# RTL8153B_DemoSCH.net
KiCad netlist of a schematic drawn in Altium Designer
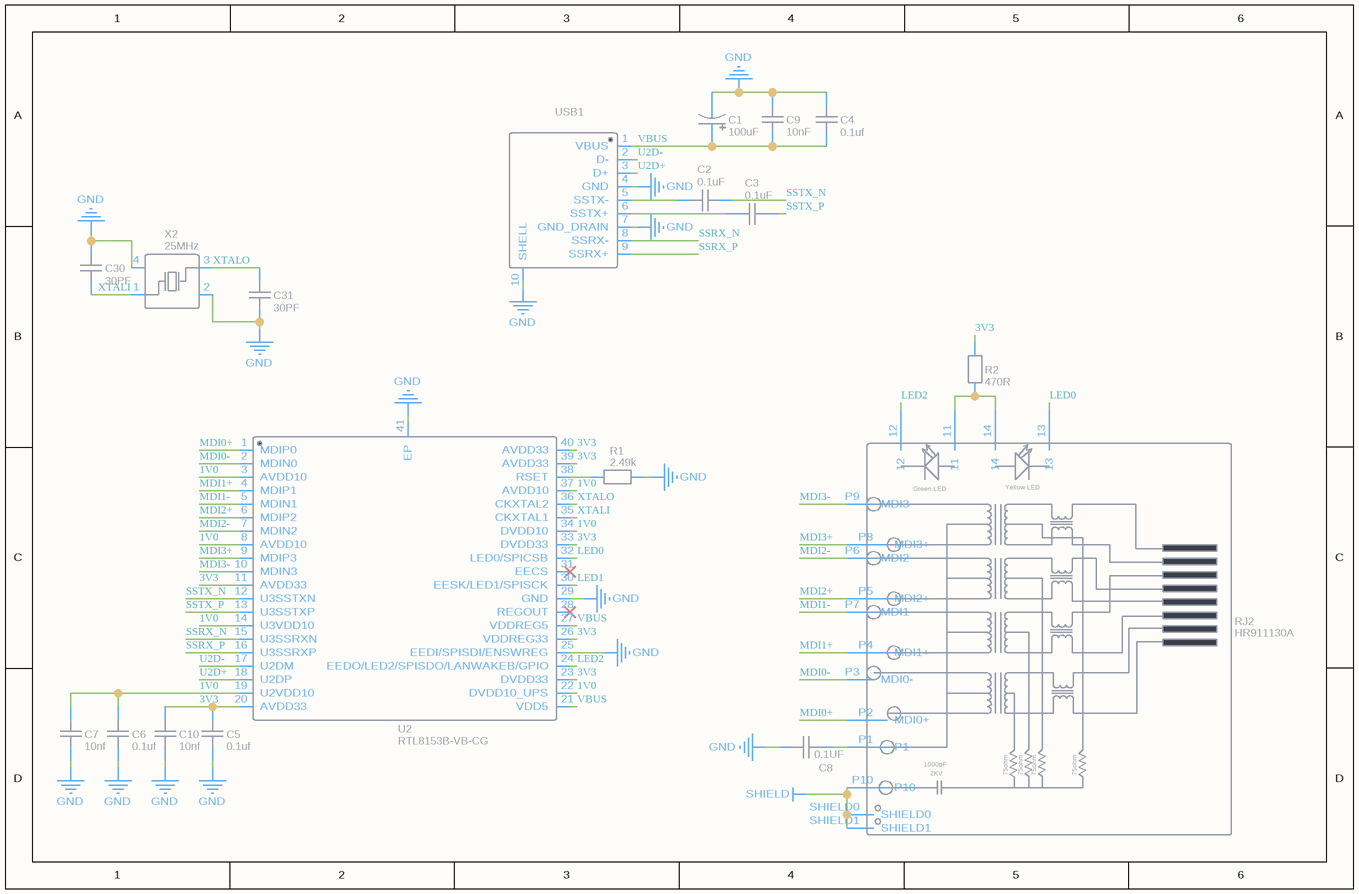
[diagram p0: RTL8153B_DemoSCH.schdoc]

(export (version "E")
  (design (tool "Eeschema 10.0.6"))
  (components
    (comp (ref "C1")
      (value "100uF")
      (fields
        (field (name "BOM_SUPPLIER PART") "C346929")
        (field (name "BOM_MANUFACTURER PART") "MVK16VC100M6.3*5_6.3TP")
        (field (name "CONTRIBUTOR") "LCSC")
      )
      (libsource (lib "altium-import") (part "root_2_100uF_"))
    )
    (comp (ref "C2")
      (value "0.1uF")
      (fields (field (name "CONTRIBUTOR") "LCEDA_Lib"))
      (libsource (lib "altium-import") (part "root_0_0.1uF_"))
    )
    (comp (ref "C3")
      (value "0.1uF")
      (fields (field (name "CONTRIBUTOR") "LCEDA_Lib"))
      (libsource (lib "altium-import") (part "root_0_0.1uF_"))
    )
    (comp (ref "C4")
      (value "0.1uf")
      (fields (field (name "CONTRIBUTOR") "LCEDA_Lib"))
      (libsource (lib "altium-import") (part "root_1_0.1uf_"))
    )
    (comp (ref "C5")
      (value "0.1uf")
      (fields (field (name "CONTRIBUTOR") "LCEDA_Lib"))
      (libsource (lib "altium-import") (part "root_1_0.1uf_"))
    )
    (comp (ref "C6")
      (value "0.1uf")
      (fields (field (name "CONTRIBUTOR") "LCEDA_Lib"))
      (libsource (lib "altium-import") (part "root_1_0.1uf_"))
    )
    (comp (ref "C7")
      (value "10nf")
      (fields (field (name "CONTRIBUTOR") "LCEDA_Lib"))
      (libsource (lib "altium-import") (part "root_1_10nf_"))
    )
    (comp (ref "C8")
      (value "0.1UF")
      (fields (field (name "CONTRIBUTOR") "LCEDA_Lib"))
      (libsource (lib "altium-import") (part "root_0_0.1UF_"))
    )
    (comp (ref "C9")
      (value "10nF")
      (fields (field (name "CONTRIBUTOR") "LCEDA_Lib"))
      (libsource (lib "altium-import") (part "root_3_10nF_"))
    )
    (comp (ref "C10")
      (value "10nf")
      (fields (field (name "CONTRIBUTOR") "LCEDA_Lib"))
      (libsource (lib "altium-import") (part "root_1_10nf_"))
    )
    (comp (ref "C30")
      (value "30PF")
      (fields (field (name "CONTRIBUTOR") "LCEDA_Lib"))
      (libsource (lib "altium-import") (part "root_1_30PF_"))
    )
    (comp (ref "C31")
      (value "30PF")
      (fields (field (name "CONTRIBUTOR") "LCEDA_Lib"))
      (libsource (lib "altium-import") (part "root_1_30PF_"))
    )
    (comp (ref "R1")
      (value "2.49k")
      (fields (field (name "CONTRIBUTOR") "LCEDA_Lib"))
      (libsource (lib "altium-import") (part "root_0_2.49k_"))
    )
    (comp (ref "R2")
      (value "470R")
      (fields (field (name "CONTRIBUTOR") "LCEDA_Lib"))
      (libsource (lib "altium-import") (part "root_1_470R_"))
    )
    (comp (ref "RJ2")
      (value "HR911130A")
      (fields (field (name "BOM_SUPPLIER PART") "C54408"))
      (libsource (lib "altium-import") (part "root_0_HR911130A_"))
    )
    (comp (ref "U2")
      (value "RTL8153B-VB-CG")
      (fields (field (name "BOM_SUPPLIER PART") "C2802072") (field (name "CONTRIBUTOR") "LCSC"))
      (libsource (lib "altium-import") (part "root_0_RTL8153B-VB-CG_"))
    )
    (comp (ref "USB1")
      (value "U3B22D-09BM4YN22HF")
      (fields (field (name "BOM_SUPPLIER PART") "C717655") (field (name "CONTRIBUTOR") "LCSC"))
      (libsource (lib "altium-import") (part "root_0_U3B22D-09BM4YN22HF_"))
    )
    (comp (ref "X2")
      (value "25MHz")
      (fields
        (field (name "BOM_SUPPLIER PART") "C164047")
        (field (name "BOM_MANUFACTURER PART") "SMD-3225_4P25MHZ12PF10PPM-40~+85℃")
        (field (name "CONTRIBUTOR") "LCSC")
      )
      (libsource (lib "altium-import") (part "root_0_25MHz_"))
    )
  )
  (nets
    (net (code "1") (name "/1V0") (class "Default")
      (node (ref "C6") (pin "2") (pinfunction "2_2") (pintype "passive"))
      (node (ref "C7") (pin "2") (pinfunction "2_2") (pintype "passive"))
      (node (ref "U2") (pin "14") (pinfunction "U3VDD10_14") (pintype "passive"))
      (node (ref "U2") (pin "19") (pinfunction "U2VDD10_19") (pintype "passive"))
      (node (ref "U2") (pin "22") (pinfunction "DVDD10_UPS_22") (pintype "passive"))
      (node (ref "U2") (pin "3") (pinfunction "AVDD10_3") (pintype "passive"))
      (node (ref "U2") (pin "34") (pinfunction "DVDD10_34") (pintype "passive"))
      (node (ref "U2") (pin "37") (pinfunction "AVDD10_37") (pintype "passive"))
      (node (ref "U2") (pin "8") (pinfunction "AVDD10_8") (pintype "passive"))
    )
    (net (code "2") (name "/3V3") (class "Default")
      (node (ref "C10") (pin "2") (pinfunction "2_2") (pintype "passive"))
      (node (ref "C5") (pin "2") (pinfunction "2_2") (pintype "passive"))
      (node (ref "R2") (pin "2") (pinfunction "2_2") (pintype "passive"))
      (node (ref "U2") (pin "11") (pinfunction "AVDD33_11") (pintype "passive"))
      (node (ref "U2") (pin "20") (pinfunction "AVDD33_20") (pintype "passive"))
      (node (ref "U2") (pin "23") (pinfunction "DVDD33_23") (pintype "passive"))
      (node (ref "U2") (pin "26") (pinfunction "VDDREG33_26") (pintype "passive"))
      (node (ref "U2") (pin "33") (pinfunction "DVDD33_33") (pintype "passive"))
      (node (ref "U2") (pin "39") (pinfunction "AVDD33_39") (pintype "passive"))
      (node (ref "U2") (pin "40") (pinfunction "AVDD33_40") (pintype "passive"))
    )
    (net (code "3") (name "/LED0") (class "Default")
      (node (ref "RJ2") (pin "13") (pinfunction "13_13") (pintype "passive"))
      (node (ref "U2") (pin "32") (pinfunction "LED0/SPICSB_32") (pintype "passive"))
    )
    (net (code "4") (name "/LED1") (class "Default")
      (node (ref "U2") (pin "30") (pinfunction "EESK/LED1/SPISCK_30") (pintype "passive"))
    )
    (net (code "5") (name "/LED2") (class "Default")
      (node (ref "RJ2") (pin "12") (pinfunction "12_12") (pintype "passive"))
      (node (ref "U2") (pin "24") (pinfunction "EEDO/LED2/SPISDO/LANWAKEB/GPIO_24") (pintype "passive"))
    )
    (net (code "6") (name "/MDI0+") (class "Default")
      (node (ref "RJ2") (pin "P2") (pinfunction "MDI0+_P2") (pintype "passive"))
      (node (ref "U2") (pin "1") (pinfunction "MDIP0_1") (pintype "passive"))
    )
    (net (code "7") (name "/MDI0-") (class "Default")
      (node (ref "RJ2") (pin "P3") (pinfunction "MDI0-_P3") (pintype "passive"))
      (node (ref "U2") (pin "2") (pinfunction "MDIN0_2") (pintype "passive"))
    )
    (net (code "8") (name "/MDI1+") (class "Default")
      (node (ref "RJ2") (pin "P4") (pinfunction "MDI1+_P4") (pintype "passive"))
      (node (ref "U2") (pin "4") (pinfunction "MDIP1_4") (pintype "passive"))
    )
    (net (code "9") (name "/MDI1-") (class "Default")
      (node (ref "RJ2") (pin "P7") (pinfunction "MDI1-_P7") (pintype "passive"))
      (node (ref "U2") (pin "5") (pinfunction "MDIN1_5") (pintype "passive"))
    )
    (net (code "10") (name "/MDI2+") (class "Default")
      (node (ref "RJ2") (pin "P5") (pinfunction "MDI2+_P5") (pintype "passive"))
      (node (ref "U2") (pin "6") (pinfunction "MDIP2_6") (pintype "passive"))
    )
    (net (code "11") (name "/MDI2-") (class "Default")
      (node (ref "RJ2") (pin "P6") (pinfunction "MDI2-_P6") (pintype "passive"))
      (node (ref "U2") (pin "7") (pinfunction "MDIN2_7") (pintype "passive"))
    )
    (net (code "12") (name "/MDI3+") (class "Default")
      (node (ref "RJ2") (pin "P8") (pinfunction "MDI3+_P8") (pintype "passive"))
      (node (ref "U2") (pin "9") (pinfunction "MDIP3_9") (pintype "passive"))
    )
    (net (code "13") (name "/MDI3-") (class "Default")
      (node (ref "RJ2") (pin "P9") (pinfunction "MDI3-_P9") (pintype "passive"))
      (node (ref "U2") (pin "10") (pinfunction "MDIN3_10") (pintype "passive"))
    )
    (net (code "14") (name "/SSRX_N") (class "Default")
      (node (ref "U2") (pin "15") (pinfunction "U3SSRXN_15") (pintype "passive"))
      (node (ref "USB1") (pin "8") (pinfunction "SSRX-_8") (pintype "passive"))
    )
    (net (code "15") (name "/SSRX_P") (class "Default")
      (node (ref "U2") (pin "16") (pinfunction "U3SSRXP_16") (pintype "passive"))
      (node (ref "USB1") (pin "9") (pinfunction "SSRX+_9") (pintype "passive"))
    )
    (net (code "16") (name "/SSTX_N") (class "Default")
      (node (ref "C2") (pin "2") (pinfunction "2_2") (pintype "passive"))
      (node (ref "U2") (pin "12") (pinfunction "U3SSTXN_12") (pintype "passive"))
    )
    (net (code "17") (name "/SSTX_P") (class "Default")
      (node (ref "C3") (pin "2") (pinfunction "2_2") (pintype "passive"))
      (node (ref "U2") (pin "13") (pinfunction "U3SSTXP_13") (pintype "passive"))
    )
    (net (code "18") (name "/U2D+") (class "Default")
      (node (ref "U2") (pin "18") (pinfunction "U2DP_18") (pintype "passive"))
      (node (ref "USB1") (pin "3") (pinfunction "D+_3") (pintype "passive"))
    )
    (net (code "19") (name "/U2D-") (class "Default")
      (node (ref "U2") (pin "17") (pinfunction "U2DM_17") (pintype "passive"))
      (node (ref "USB1") (pin "2") (pinfunction "D-_2") (pintype "passive"))
    )
    (net (code "20") (name "/VBUS") (class "Default")
      (node (ref "C1") (pin "1") (pinfunction "1_1") (pintype "passive"))
      (node (ref "C4") (pin "1") (pinfunction "1_1") (pintype "passive"))
      (node (ref "C9") (pin "2") (pinfunction "2_2") (pintype "passive"))
      (node (ref "U2") (pin "21") (pinfunction "VDD5_21") (pintype "passive"))
      (node (ref "U2") (pin "27") (pinfunction "VDDREG5_27") (pintype "passive"))
      (node (ref "USB1") (pin "1") (pinfunction "VBUS_1") (pintype "passive"))
    )
    (net (code "21") (name "/XTALI") (class "Default")
      (node (ref "C30") (pin "1") (pinfunction "1_1") (pintype "passive"))
      (node (ref "U2") (pin "35") (pinfunction "CKXTAL1_35") (pintype "passive"))
      (node (ref "X2") (pin "1") (pinfunction "OSC1_1") (pintype "passive"))
    )
    (net (code "22") (name "/XTALO") (class "Default")
      (node (ref "C31") (pin "2") (pinfunction "2_2") (pintype "passive"))
      (node (ref "U2") (pin "36") (pinfunction "CKXTAL2_36") (pintype "passive"))
      (node (ref "X2") (pin "3") (pinfunction "OSC2_3") (pintype "passive"))
    )
    (net (code "23") (name "GND") (class "Default")
      (node (ref "C1") (pin "2") (pinfunction "2_2") (pintype "passive"))
      (node (ref "C10") (pin "1") (pinfunction "1_1") (pintype "passive"))
      (node (ref "C30") (pin "2") (pinfunction "2_2") (pintype "passive"))
      (node (ref "C31") (pin "1") (pinfunction "1_1") (pintype "passive"))
      (node (ref "C4") (pin "2") (pinfunction "2_2") (pintype "passive"))
      (node (ref "C5") (pin "1") (pinfunction "1_1") (pintype "passive"))
      (node (ref "C6") (pin "1") (pinfunction "1_1") (pintype "passive"))
      (node (ref "C7") (pin "1") (pinfunction "1_1") (pintype "passive"))
      (node (ref "C8") (pin "1") (pinfunction "1_1") (pintype "passive"))
      (node (ref "C9") (pin "1") (pinfunction "1_1") (pintype "passive"))
      (node (ref "R1") (pin "2") (pinfunction "2_2") (pintype "passive"))
      (node (ref "U2") (pin "25") (pinfunction "EEDI/SPISDI/ENSWREG_25") (pintype "passive"))
      (node (ref "U2") (pin "29") (pinfunction "GND_29") (pintype "passive"))
      (node (ref "U2") (pin "41") (pinfunction "EP_41") (pintype "passive"))
      (node (ref "USB1") (pin "10") (pinfunction "SHELL_10") (pintype "passive"))
      (node (ref "USB1") (pin "4") (pinfunction "GND_4") (pintype "passive"))
      (node (ref "USB1") (pin "7") (pinfunction "GND_DRAIN_7") (pintype "passive"))
      (node (ref "X2") (pin "2") (pinfunction "GND_2") (pintype "passive"))
      (node (ref "X2") (pin "4") (pinfunction "GND_4") (pintype "passive"))
    )
    (net (code "24") (name "Net-(C8-Pad2)") (class "Default")
      (node (ref "C8") (pin "2") (pinfunction "2_2") (pintype "passive"))
      (node (ref "RJ2") (pin "P1") (pinfunction "P1_P1") (pintype "passive"))
    )
    (net (code "25") (name "Net-(R2-Pad1)") (class "Default")
      (node (ref "R2") (pin "1") (pinfunction "1_1") (pintype "passive"))
      (node (ref "RJ2") (pin "11") (pinfunction "11_11") (pintype "passive"))
      (node (ref "RJ2") (pin "14") (pinfunction "14_14") (pintype "passive"))
    )
    (net (code "26") (name "Net-(U2-RSET)") (class "Default")
      (node (ref "R1") (pin "1") (pinfunction "1_1") (pintype "passive"))
      (node (ref "U2") (pin "38") (pinfunction "RSET_38") (pintype "passive"))
    )
    (net (code "27") (name "Net-(USB1-SSTX+)") (class "Default")
      (node (ref "C3") (pin "1") (pinfunction "1_1") (pintype "passive"))
      (node (ref "USB1") (pin "6") (pinfunction "SSTX+_6") (pintype "passive"))
    )
    (net (code "28") (name "Net-(USB1-SSTX-)") (class "Default")
      (node (ref "C2") (pin "1") (pinfunction "1_1") (pintype "passive"))
      (node (ref "USB1") (pin "5") (pinfunction "SSTX-_5") (pintype "passive"))
    )
    (net (code "29") (name "SHIELD") (class "Default")
      (node (ref "RJ2") (pin "P10") (pinfunction "P10_P10") (pintype "passive"))
      (node (ref "RJ2") (pin "SHIELD0") (pinfunction "SHIELD0_SHIELD0") (pintype "passive"))
      (node (ref "RJ2") (pin "SHIELD1") (pinfunction "SHIELD1_SHIELD1") (pintype "passive"))
    )
    (net (code "30") (name "unconnected-(U2-EECS-Pad31)") (class "Default")
      (node (ref "U2") (pin "31") (pinfunction "EECS_31") (pintype "passive+no_connect"))
    )
    (net (code "31") (name "unconnected-(U2-REGOUT-Pad28)") (class "Default")
      (node (ref "U2") (pin "28") (pinfunction "REGOUT_28") (pintype "passive+no_connect"))
    )
  )
)
